# microSD.net
KiCad netlist of a schematic drawn in Altium Designer
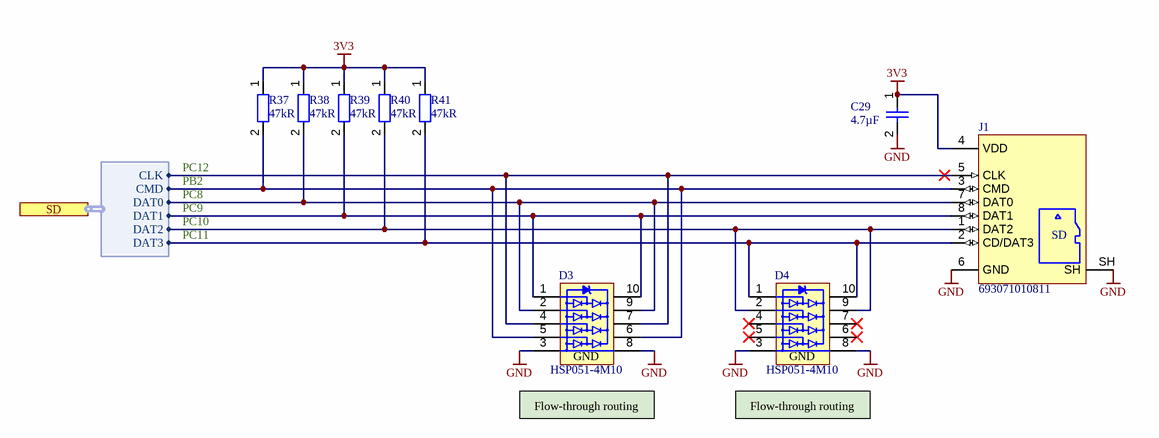
[diagram p0: microSD.SchDoc]

(export (version "E")
  (design (tool "Eeschema 10.0.6"))
  (components
    (comp (ref "C29")
      (value "4.7µF")
      (footprint "CAPC1608X80N")
      (description "Cap MLCC, 4.7uF, 16V, X7R, 10%, 0603")
      (fields (field (name "TOLERANCE") "10%") (field (name "Comment") "4.7uF/16V"))
      (libsource (lib "ZHAW on Altium 365") (part "CAP-NP-2"))
    )
    (comp (ref "D3")
      (value "HSP051-4M10")
      (footprint "QFN50P100X250X50-10")
      (libsource (lib "ZHAW on Altium 365") (part "D-TVS-HSP051-4M10-10"))
    )
    (comp (ref "D4")
      (value "HSP051-4M10")
      (footprint "QFN50P100X250X50-10")
      (libsource (lib "ZHAW on Altium 365") (part "D-TVS-HSP051-4M10-10"))
    )
    (comp (ref "J1")
      (value "693071010811")
      (footprint "WE_693071010811")
      (description "SD-Card Micro Connector, 8 Position, Push In, Push Out, SMD")
      (fields (field (name "MANUFACTURER") "Würth"))
      (libsource (lib "ZHAW on Altium 365") (part "CN-SDCARD-SH-8"))
    )
    (comp (ref "R37")
      (value "47kR")
      (footprint "RESC1005X35N")
      (description "Res, 47kR, 1%, 0.063W, 0402")
      (fields (field (name "TOLERANCE") "1%") (field (name "POWER") "63mW"))
      (libsource (lib "ZHAW on Altium 365") (part "RES-2"))
    )
    (comp (ref "R38")
      (value "47kR")
      (footprint "RESC1005X35N")
      (description "Res, 47kR, 1%, 0.063W, 0402")
      (fields (field (name "TOLERANCE") "1%") (field (name "POWER") "63mW"))
      (libsource (lib "ZHAW on Altium 365") (part "RES-2"))
    )
    (comp (ref "R39")
      (value "47kR")
      (footprint "RESC1005X35N")
      (description "Res, 47kR, 1%, 0.063W, 0402")
      (fields (field (name "TOLERANCE") "1%") (field (name "POWER") "63mW"))
      (libsource (lib "ZHAW on Altium 365") (part "RES-2"))
    )
    (comp (ref "R40")
      (value "47kR")
      (footprint "RESC1005X35N")
      (description "Res, 47kR, 1%, 0.063W, 0402")
      (fields (field (name "TOLERANCE") "1%") (field (name "POWER") "63mW"))
      (libsource (lib "ZHAW on Altium 365") (part "RES-2"))
    )
    (comp (ref "R41")
      (value "47kR")
      (footprint "RESC1005X35N")
      (description "Res, 47kR, 1%, 0.063W, 0402")
      (fields (field (name "TOLERANCE") "1%") (field (name "POWER") "63mW"))
      (libsource (lib "ZHAW on Altium 365") (part "RES-2"))
    )
  )
  (nets
    (net (code "3") (name "3V3") (class "Default")
      (node (ref "C29") (pin "1") (pinfunction "1_1") (pintype "passive"))
      (node (ref "J1") (pin "4") (pinfunction "VDD_4") (pintype "power_in"))
      (node (ref "R37") (pin "1") (pinfunction "1_1") (pintype "passive"))
      (node (ref "R38") (pin "1") (pinfunction "1_1") (pintype "passive"))
      (node (ref "R39") (pin "1") (pinfunction "1_1") (pintype "passive"))
      (node (ref "R40") (pin "1") (pinfunction "1_1") (pintype "passive"))
      (node (ref "R41") (pin "1") (pinfunction "1_1") (pintype "passive"))
    )
    (net (code "4") (name "GND") (class "Default")
      (node (ref "C29") (pin "2") (pinfunction "2_2") (pintype "passive"))
      (node (ref "D3") (pin "3") (pinfunction "GND_3") (pintype "passive"))
      (node (ref "D3") (pin "8") (pinfunction "GND_8") (pintype "passive"))
      (node (ref "D4") (pin "3") (pinfunction "GND_3") (pintype "passive"))
      (node (ref "D4") (pin "8") (pinfunction "GND_8") (pintype "passive"))
      (node (ref "J1") (pin "6") (pinfunction "GND_6") (pintype "passive"))
      (node (ref "J1") (pin "SH") (pinfunction "SH_SH") (pintype "passive"))
    )
    (net (code "5") (name "Net-(D3-I{slash}O1)") (class "Default")
      (node (ref "D3") (pin "1") (pinfunction "I/O1_1") (pintype "passive"))
      (node (ref "D3") (pin "10") (pinfunction "NC_10") (pintype "passive"))
      (node (ref "J1") (pin "8") (pinfunction "DAT1_8") (pintype "bidirectional"))
      (node (ref "R39") (pin "2") (pinfunction "2_2") (pintype "passive"))
    )
    (net (code "6") (name "Net-(D3-I{slash}O2)") (class "Default")
      (node (ref "D3") (pin "2") (pinfunction "I/O2_2") (pintype "passive"))
      (node (ref "D3") (pin "9") (pinfunction "NC_9") (pintype "passive"))
      (node (ref "J1") (pin "7") (pinfunction "DAT0_7") (pintype "bidirectional"))
      (node (ref "R38") (pin "2") (pinfunction "2_2") (pintype "passive"))
    )
    (net (code "7") (name "Net-(D3-I{slash}O3)") (class "Default")
      (node (ref "D3") (pin "4") (pinfunction "I/O3_4") (pintype "passive"))
      (node (ref "D3") (pin "7") (pinfunction "NC_7") (pintype "passive"))
      (node (ref "J1") (pin "5") (pinfunction "CLK_5") (pintype "input"))
    )
    (net (code "8") (name "Net-(D3-I{slash}O4)") (class "Default")
      (node (ref "D3") (pin "5") (pinfunction "I/O4_5") (pintype "passive"))
      (node (ref "D3") (pin "6") (pinfunction "NC_6") (pintype "passive"))
      (node (ref "J1") (pin "3") (pinfunction "CMD_3") (pintype "bidirectional"))
      (node (ref "R37") (pin "2") (pinfunction "2_2") (pintype "passive"))
    )
    (net (code "9") (name "Net-(D4-I{slash}O1)") (class "Default")
      (node (ref "D4") (pin "1") (pinfunction "I/O1_1") (pintype "passive"))
      (node (ref "D4") (pin "10") (pinfunction "NC_10") (pintype "passive"))
      (node (ref "J1") (pin "2") (pinfunction "CD/DAT3_2") (pintype "bidirectional"))
      (node (ref "R41") (pin "2") (pinfunction "2_2") (pintype "passive"))
    )
    (net (code "10") (name "Net-(D4-I{slash}O2)") (class "Default")
      (node (ref "D4") (pin "2") (pinfunction "I/O2_2") (pintype "passive"))
      (node (ref "D4") (pin "9") (pinfunction "NC_9") (pintype "passive"))
      (node (ref "J1") (pin "1") (pinfunction "DAT2_1") (pintype "bidirectional"))
      (node (ref "R40") (pin "2") (pinfunction "2_2") (pintype "passive"))
    )
    (net (code "11") (name "unconnected-(D4-I{slash}O3-Pad4)") (class "Default")
      (node (ref "D4") (pin "4") (pinfunction "I/O3_4") (pintype "passive+no_connect"))
    )
    (net (code "12") (name "unconnected-(D4-I{slash}O4-Pad5)") (class "Default")
      (node (ref "D4") (pin "5") (pinfunction "I/O4_5") (pintype "passive+no_connect"))
    )
    (net (code "13") (name "unconnected-(D4-NC-Pad6)") (class "Default")
      (node (ref "D4") (pin "6") (pinfunction "NC_6") (pintype "passive+no_connect"))
    )
    (net (code "14") (name "unconnected-(D4-NC-Pad7)") (class "Default")
      (node (ref "D4") (pin "7") (pinfunction "NC_7") (pintype "passive+no_connect"))
    )
  )
)
